# CON2.net
KiCad netlist of a schematic drawn in Altium Designer
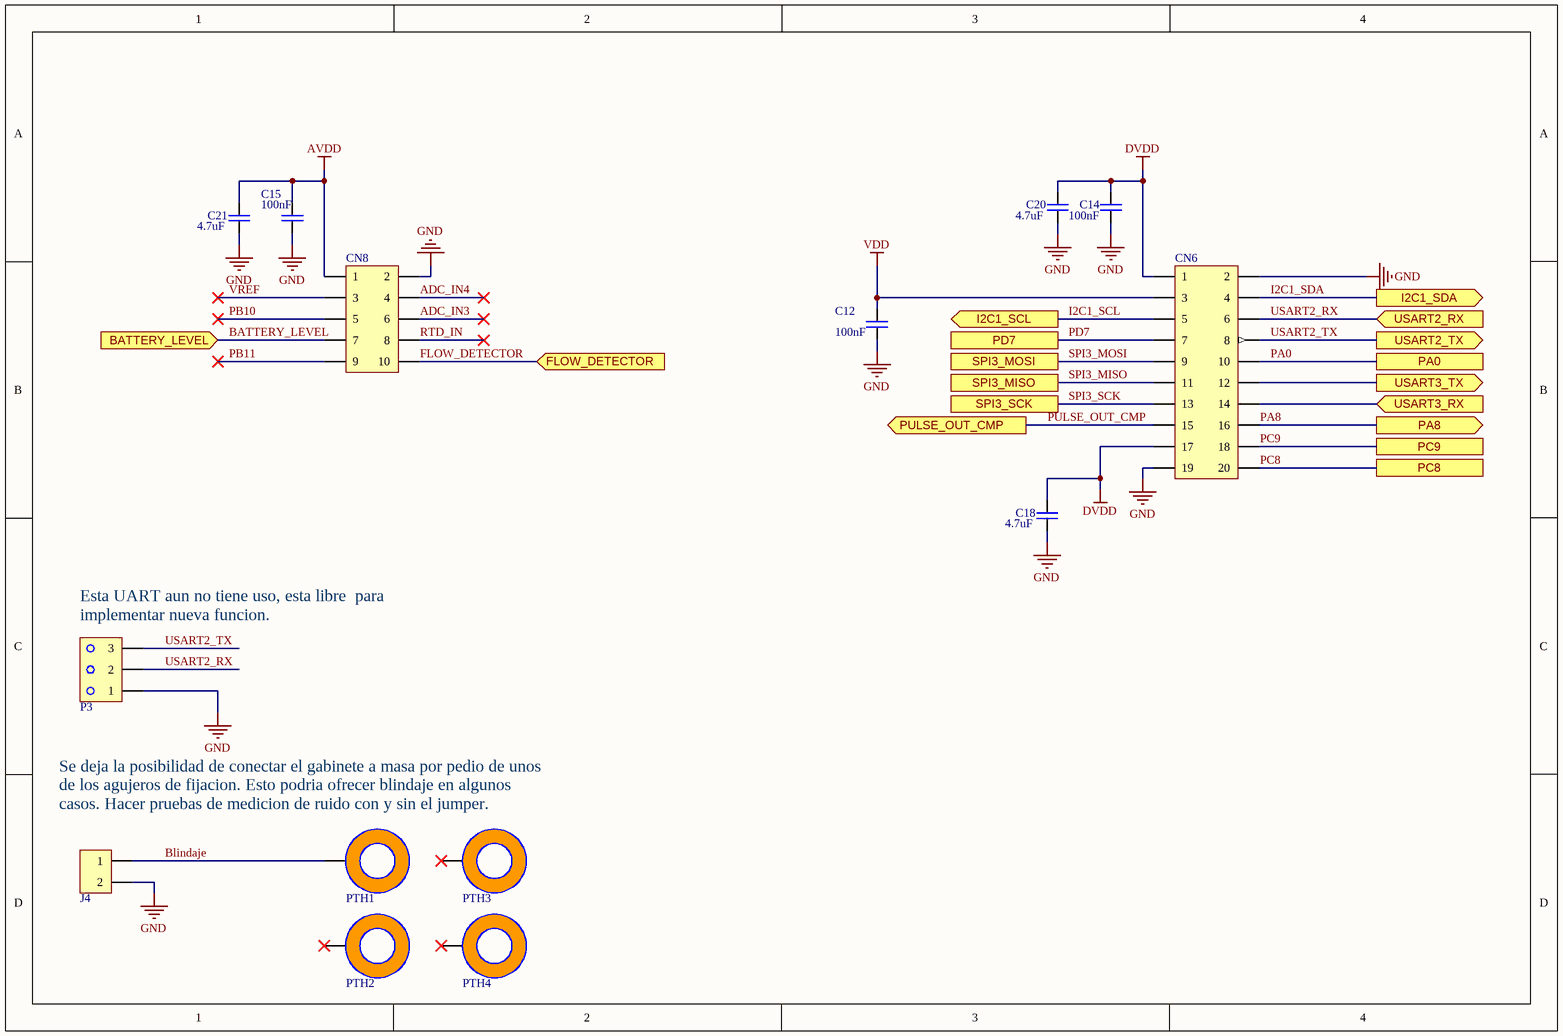
[diagram p0: CON2.SchDoc]

(export (version "E")
  (design (tool "Eeschema 10.0.6"))
  (components
    (comp (ref "C12")
      (value "100nF")
      (footprint "CAP_SM0805_YAGEOCC2_N")
      (description "CAP 100nF SM0805 X7R 25V YAGEO CC2")
      (fields
        (field (name "MANUFACTURER") "Yageo")
        (field (name "MANUFACTURER PART NUMBER") "CC0805KRX7R8BB104")
      )
      (libsource (lib "Yageo") (part "CC0805KRX7R8BB104"))
    )
    (comp (ref "C14")
      (value "100nF")
      (footprint "CAP_SM0805_YAGEOCC2_N")
      (description "CAP 100nF SM0805 X7R 25V YAGEO CC2")
      (fields
        (field (name "MANUFACTURER") "Yageo")
        (field (name "MANUFACTURER PART NUMBER") "CC0805KRX7R8BB104")
      )
      (libsource (lib "Yageo") (part "CC0805KRX7R8BB104"))
    )
    (comp (ref "C15")
      (value "100nF")
      (footprint "CAP_SM0805_YAGEOCC2_N")
      (description "CAP 100nF SM0805 X7R 25V YAGEO CC2")
      (fields
        (field (name "MANUFACTURER") "Yageo")
        (field (name "MANUFACTURER PART NUMBER") "CC0805KRX7R8BB104")
      )
      (libsource (lib "Yageo") (part "CC0805KRX7R8BB104"))
    )
    (comp (ref "C18")
      (value "4.7uF")
      (footprint "CAP_SM0805_YAGEOCC2_N")
      (description "CAP 4.7uF SM0805 X5R 10V YAGEO CC2")
      (fields
        (field (name "MANUFACTURER") "Yageo")
        (field (name "MANUFACTURER PART NUMBER") "CC0805KRX5R6BB475")
      )
      (libsource (lib "Yageo") (part "CC0805KRX5R6BB475"))
    )
    (comp (ref "C20")
      (value "4.7uF")
      (footprint "CAP_SM0805_YAGEOCC2_N")
      (description "CAP 4.7uF SM0805 X5R 10V YAGEO CC2")
      (fields
        (field (name "MANUFACTURER") "Yageo")
        (field (name "MANUFACTURER PART NUMBER") "CC0805KRX5R6BB475")
      )
      (libsource (lib "Yageo") (part "CC0805KRX5R6BB475"))
    )
    (comp (ref "C21")
      (value "4.7uF")
      (footprint "CAP_SM0805_YAGEOCC2_N")
      (description "CAP 4.7uF SM0805 X5R 10V YAGEO CC2")
      (fields
        (field (name "MANUFACTURER") "Yageo")
        (field (name "MANUFACTURER PART NUMBER") "CC0805KRX5R6BB475")
      )
      (libsource (lib "Yageo") (part "CC0805KRX5R6BB475"))
    )
    (comp (ref "CN6")
      (value "DZ254R-22-20-63")
      (footprint "HEADER PIN 2X10")
      (description "2 x 10 - true hole 2.54mm")
      (fields (field (name "MANUFACTURER") "DEALON"))
      (libsource (lib "header_pin") (part "DZ254R-22-20-63"))
    )
    (comp (ref "CN8")
      (value "Uar Equivalente")
      (footprint "HEADER PIN 2X5 MIRROR")
      (description "2 x 5 - true hole 2.54mm")
      (fields
        (field (name "MANUFACTURER") "DEALON")
        (field (name "MANUFACTURER PART NUMBER") "DZ254R-22-10-63")
      )
      (libsource (lib "header_pin") (part "DZ254R-22-10-63"))
    )
    (comp (ref "J4")
      (value "Usar Equivalente")
      (footprint "HEADER PIN 1X2")
      (description "1 x 2 - true hole  2.54mm - Pb free")
      (fields
        (field (name "MANUFACTURER") "Amphenol ICC")
        (field (name "MANUFACTURER PART NUMBER") "54101-T0600LF")
      )
      (libsource (lib "header_pin") (part "54101-T0600LF-CUT-2"))
    )
    (comp (ref "P3")
      (value "WJ15EDGVC-3.81-3P")
      (footprint "HEADER PLUG 3")
      (description "TERM BLOK FEMALE 1X3 3.81MM")
      (fields (field (name "MANUFACTURER") "Ningbo Kangnex Elec"))
      (libsource (lib "plug") (part "WJ15EDGVC-3.81-3P"))
    )
    (comp (ref "PTH1")
      (value "PTH-3MM-M")
      (footprint "PTH_M3_M")
      (description "Agujero de montaje metalizado roscas M3. Drill de tamaño medio.")
      (libsource (lib "montaje") (part "PTH-3MM-M"))
    )
    (comp (ref "PTH2")
      (value "PTH-3MM-M")
      (footprint "PTH_M3_M")
      (description "Agujero de montaje metalizado roscas M3. Drill de tamaño medio.")
      (libsource (lib "montaje") (part "PTH-3MM-M"))
    )
    (comp (ref "PTH3")
      (value "PTH-3MM-M")
      (footprint "PTH_M3_M")
      (description "Agujero de montaje metalizado roscas M3. Drill de tamaño medio.")
      (libsource (lib "montaje") (part "PTH-3MM-M"))
    )
    (comp (ref "PTH4")
      (value "PTH-3MM-M")
      (footprint "PTH_M3_M")
      (description "Agujero de montaje metalizado roscas M3. Drill de tamaño medio.")
      (libsource (lib "montaje") (part "PTH-3MM-M"))
    )
  )
  (nets
    (net (code "1") (name "/ADC_IN3") (class "Default")
      (node (ref "CN8") (pin "6") (pinfunction "6_6") (pintype "passive+no_connect"))
    )
    (net (code "2") (name "/ADC_IN4") (class "Default")
      (node (ref "CN8") (pin "4") (pinfunction "4_4") (pintype "passive+no_connect"))
    )
    (net (code "3") (name "/BATTERY_LEVEL") (class "Default")
      (node (ref "CN8") (pin "7") (pinfunction "7_7") (pintype "passive"))
    )
    (net (code "4") (name "/Blindaje") (class "Default")
      (node (ref "J4") (pin "1") (pinfunction "1_1") (pintype "passive"))
      (node (ref "PTH1") (pin "1") (pinfunction "1_1") (pintype "passive"))
    )
    (net (code "5") (name "/FLOW_DETECTOR") (class "Default")
      (node (ref "CN8") (pin "10") (pinfunction "10_10") (pintype "passive"))
    )
    (net (code "6") (name "/I2C1_SCL") (class "Default")
      (node (ref "CN6") (pin "5") (pinfunction "5_5") (pintype "passive"))
    )
    (net (code "7") (name "/I2C1_SDA") (class "Default")
      (node (ref "CN6") (pin "4") (pinfunction "4_4") (pintype "passive"))
    )
    (net (code "8") (name "/PA0") (class "Default")
      (node (ref "CN6") (pin "10") (pinfunction "10_10") (pintype "passive"))
    )
    (net (code "9") (name "/PA8") (class "Default")
      (node (ref "CN6") (pin "16") (pinfunction "16_16") (pintype "passive"))
    )
    (net (code "10") (name "/PB10") (class "Default")
      (node (ref "CN8") (pin "5") (pinfunction "5_5") (pintype "passive+no_connect"))
    )
    (net (code "11") (name "/PB11") (class "Default")
      (node (ref "CN8") (pin "9") (pinfunction "9_9") (pintype "passive+no_connect"))
    )
    (net (code "12") (name "/PC8") (class "Default")
      (node (ref "CN6") (pin "20") (pinfunction "20_20") (pintype "passive"))
    )
    (net (code "13") (name "/PC9") (class "Default")
      (node (ref "CN6") (pin "18") (pinfunction "18_18") (pintype "passive"))
    )
    (net (code "14") (name "/PD7") (class "Default")
      (node (ref "CN6") (pin "7") (pinfunction "7_7") (pintype "passive"))
    )
    (net (code "15") (name "/PULSE_OUT_CMP") (class "Default")
      (node (ref "CN6") (pin "15") (pinfunction "15_15") (pintype "passive"))
    )
    (net (code "16") (name "/RTD_IN") (class "Default")
      (node (ref "CN8") (pin "8") (pinfunction "8_8") (pintype "passive+no_connect"))
    )
    (net (code "17") (name "/SPI3_MISO") (class "Default")
      (node (ref "CN6") (pin "11") (pinfunction "11_11") (pintype "passive"))
    )
    (net (code "18") (name "/SPI3_MOSI") (class "Default")
      (node (ref "CN6") (pin "9") (pinfunction "9_9") (pintype "passive"))
    )
    (net (code "19") (name "/SPI3_SCK") (class "Default")
      (node (ref "CN6") (pin "13") (pinfunction "13_13") (pintype "passive"))
    )
    (net (code "20") (name "/USART2_RX") (class "Default")
      (node (ref "CN6") (pin "6") (pinfunction "6_6") (pintype "passive"))
      (node (ref "P3") (pin "2") (pinfunction "2_2") (pintype "passive"))
    )
    (net (code "21") (name "/USART2_TX") (class "Default")
      (node (ref "CN6") (pin "8") (pinfunction "8_8") (pintype "output"))
      (node (ref "P3") (pin "3") (pinfunction "3_3") (pintype "passive"))
    )
    (net (code "22") (name "/USART3_RX") (class "Default")
      (node (ref "CN6") (pin "14") (pinfunction "14_14") (pintype "passive"))
    )
    (net (code "23") (name "/USART3_TX") (class "Default")
      (node (ref "CN6") (pin "12") (pinfunction "12_12") (pintype "passive"))
    )
    (net (code "24") (name "/VREF") (class "Default")
      (node (ref "CN8") (pin "3") (pinfunction "3_3") (pintype "passive+no_connect"))
    )
    (net (code "25") (name "AVDD") (class "Default")
      (node (ref "C15") (pin "1") (pintype "passive"))
      (node (ref "C21") (pin "1") (pintype "passive"))
      (node (ref "CN8") (pin "1") (pinfunction "1_1") (pintype "passive"))
    )
    (net (code "26") (name "DVDD") (class "Default")
      (node (ref "C14") (pin "1") (pintype "passive"))
      (node (ref "C18") (pin "1") (pintype "passive"))
      (node (ref "C20") (pin "1") (pintype "passive"))
      (node (ref "CN6") (pin "1") (pinfunction "1_1") (pintype "passive"))
      (node (ref "CN6") (pin "17") (pinfunction "17_17") (pintype "passive"))
    )
    (net (code "27") (name "GND") (class "Default")
      (node (ref "C12") (pin "2") (pintype "passive"))
      (node (ref "C14") (pin "2") (pintype "passive"))
      (node (ref "C15") (pin "2") (pintype "passive"))
      (node (ref "C18") (pin "2") (pintype "passive"))
      (node (ref "C20") (pin "2") (pintype "passive"))
      (node (ref "C21") (pin "2") (pintype "passive"))
      (node (ref "CN6") (pin "19") (pinfunction "19_19") (pintype "passive"))
      (node (ref "CN6") (pin "2") (pinfunction "2_2") (pintype "passive"))
      (node (ref "CN8") (pin "2") (pinfunction "2_2") (pintype "passive"))
      (node (ref "J4") (pin "2") (pinfunction "2_2") (pintype "passive"))
      (node (ref "P3") (pin "1") (pinfunction "1_1") (pintype "passive"))
    )
    (net (code "28") (name "VDD") (class "Default")
      (node (ref "C12") (pin "1") (pintype "passive"))
      (node (ref "CN6") (pin "3") (pinfunction "3_3") (pintype "passive"))
    )
    (net (code "29") (name "unconnected-(PTH2-Pad1)") (class "Default")
      (node (ref "PTH2") (pin "1") (pinfunction "1_1") (pintype "passive+no_connect"))
    )
    (net (code "30") (name "unconnected-(PTH3-Pad1)") (class "Default")
      (node (ref "PTH3") (pin "1") (pinfunction "1_1") (pintype "passive+no_connect"))
    )
    (net (code "31") (name "unconnected-(PTH4-Pad1)") (class "Default")
      (node (ref "PTH4") (pin "1") (pinfunction "1_1") (pintype "passive+no_connect"))
    )
  )
)
